# GPIO_Test.net
KiCad netlist of a schematic drawn in Altium Designer
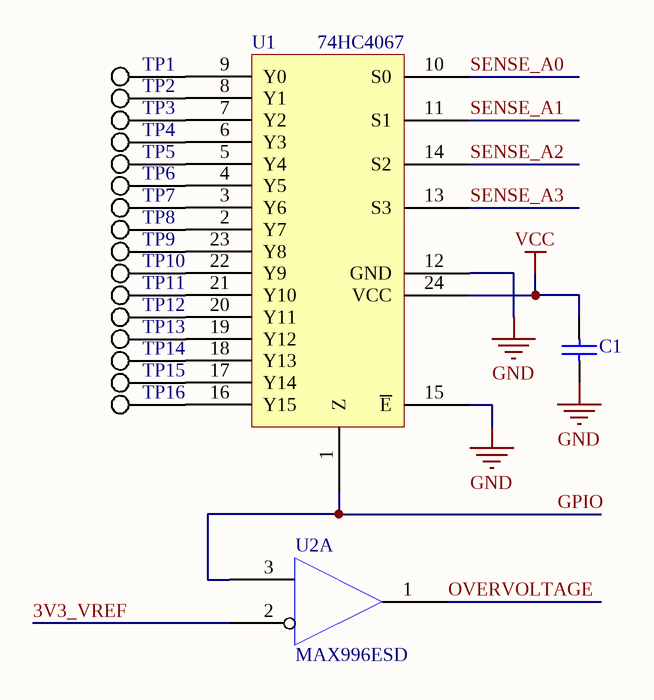
[diagram p0: GPIO Test.SchDoc]

(export (version "E")
  (design (tool "Eeschema 10.0.6"))
  (components
    (comp (ref "C1")
      (value "Cap chip")
      (footprint "CAPC3216")
      (description "Chip Capacitor")
      (fields (field (name "PUBLISHER") "Altium Limited"))
      (libsource (lib "Common Devices") (part "Cap chip"))
    )
    (comp (ref "TP1") (value "Test point") (libsource (lib "PCB_Project") (part "Pogo Test Pin")))
    (comp (ref "TP2") (value "Test point") (libsource (lib "PCB_Project") (part "Pogo Test Pin")))
    (comp (ref "TP3") (value "Test point") (libsource (lib "PCB_Project") (part "Pogo Test Pin")))
    (comp (ref "TP4") (value "Test point") (libsource (lib "PCB_Project") (part "Pogo Test Pin")))
    (comp (ref "TP5") (value "Test point") (libsource (lib "PCB_Project") (part "Pogo Test Pin")))
    (comp (ref "TP6") (value "Test point") (libsource (lib "PCB_Project") (part "Pogo Test Pin")))
    (comp (ref "TP7") (value "Test point") (libsource (lib "PCB_Project") (part "Pogo Test Pin")))
    (comp (ref "TP8") (value "Test point") (libsource (lib "PCB_Project") (part "Pogo Test Pin")))
    (comp (ref "TP9") (value "Test point") (libsource (lib "PCB_Project") (part "Pogo Test Pin")))
    (comp (ref "TP10") (value "Test point") (libsource (lib "PCB_Project") (part "Pogo Test Pin")))
    (comp (ref "TP11") (value "Test point") (libsource (lib "PCB_Project") (part "Pogo Test Pin")))
    (comp (ref "TP12") (value "Test point") (libsource (lib "PCB_Project") (part "Pogo Test Pin")))
    (comp (ref "TP13") (value "Test point") (libsource (lib "PCB_Project") (part "Pogo Test Pin")))
    (comp (ref "TP14") (value "Test point") (libsource (lib "PCB_Project") (part "Pogo Test Pin")))
    (comp (ref "TP15") (value "Test point") (libsource (lib "PCB_Project") (part "Pogo Test Pin")))
    (comp (ref "TP16") (value "Test point") (libsource (lib "PCB_Project") (part "Pogo Test Pin")))
    (comp (ref "U1")
      (value "74HC4067")
      (footprint "SO24")
      (description "16-channel analog multiplexer/demultiplexer")
      (libsource (lib "PCB_Project") (part "74HC4067; 74HCT4067"))
    )
    (comp (ref "U2")
      (value "MAX996ESD")
      (footprint "SOIC-14")
      (description "High-Speed, Micropower, Low-Voltage,  Rail-to-Rail I/O Comparators")
      (libsource (lib "PCB_Project") (part "MAX996ESD"))
    )
  )
  (nets
    (net (code "1") (name "/3V3_VREF") (class "Default")
      (node (ref "U2") (pin "2") (pinfunction "-IN1_2") (pintype "passive"))
    )
    (net (code "2") (name "/GPIO") (class "Default")
      (node (ref "U1") (pin "1") (pinfunction "Z_1") (pintype "passive"))
      (node (ref "U2") (pin "3") (pinfunction "+IN1_3") (pintype "passive"))
    )
    (net (code "3") (name "/OVERVOLTAGE") (class "Default")
      (node (ref "U2") (pin "1") (pinfunction "OUT1_1") (pintype "passive"))
    )
    (net (code "4") (name "/SENSE_A0") (class "Default")
      (node (ref "U1") (pin "10") (pinfunction "S0_10") (pintype "passive"))
    )
    (net (code "5") (name "/SENSE_A1") (class "Default")
      (node (ref "U1") (pin "11") (pinfunction "S1_11") (pintype "passive"))
    )
    (net (code "6") (name "/SENSE_A2") (class "Default")
      (node (ref "U1") (pin "14") (pinfunction "S2_14") (pintype "passive"))
    )
    (net (code "7") (name "/SENSE_A3") (class "Default")
      (node (ref "U1") (pin "13") (pinfunction "S3_13") (pintype "passive"))
    )
    (net (code "8") (name "GND") (class "Default")
      (node (ref "C1") (pin "1") (pinfunction "1_1") (pintype "passive"))
      (node (ref "U1") (pin "12") (pinfunction "GND_12") (pintype "passive"))
      (node (ref "U1") (pin "15") (pinfunction "~{E}_15") (pintype "passive"))
    )
    (net (code "9") (name "Net-(U1-Y0)") (class "Default")
      (node (ref "TP1") (pin "1") (pinfunction "1_1") (pintype "passive"))
      (node (ref "U1") (pin "9") (pinfunction "Y0_9") (pintype "passive"))
    )
    (net (code "10") (name "Net-(U1-Y1)") (class "Default")
      (node (ref "TP2") (pin "1") (pinfunction "1_1") (pintype "passive"))
      (node (ref "U1") (pin "8") (pinfunction "Y1_8") (pintype "passive"))
    )
    (net (code "11") (name "Net-(U1-Y2)") (class "Default")
      (node (ref "TP3") (pin "1") (pinfunction "1_1") (pintype "passive"))
      (node (ref "U1") (pin "7") (pinfunction "Y2_7") (pintype "passive"))
    )
    (net (code "12") (name "Net-(U1-Y3)") (class "Default")
      (node (ref "TP4") (pin "1") (pinfunction "1_1") (pintype "passive"))
      (node (ref "U1") (pin "6") (pinfunction "Y3_6") (pintype "passive"))
    )
    (net (code "13") (name "Net-(U1-Y4)") (class "Default")
      (node (ref "TP5") (pin "1") (pinfunction "1_1") (pintype "passive"))
      (node (ref "U1") (pin "5") (pinfunction "Y4_5") (pintype "passive"))
    )
    (net (code "14") (name "Net-(U1-Y5)") (class "Default")
      (node (ref "TP6") (pin "1") (pinfunction "1_1") (pintype "passive"))
      (node (ref "U1") (pin "4") (pinfunction "Y5_4") (pintype "passive"))
    )
    (net (code "15") (name "Net-(U1-Y6)") (class "Default")
      (node (ref "TP7") (pin "1") (pinfunction "1_1") (pintype "passive"))
      (node (ref "U1") (pin "3") (pinfunction "Y6_3") (pintype "passive"))
    )
    (net (code "16") (name "Net-(U1-Y7)") (class "Default")
      (node (ref "TP8") (pin "1") (pinfunction "1_1") (pintype "passive"))
      (node (ref "U1") (pin "2") (pinfunction "Y7_2") (pintype "passive"))
    )
    (net (code "17") (name "Net-(U1-Y8)") (class "Default")
      (node (ref "TP9") (pin "1") (pinfunction "1_1") (pintype "passive"))
      (node (ref "U1") (pin "23") (pinfunction "Y8_23") (pintype "passive"))
    )
    (net (code "18") (name "Net-(U1-Y9)") (class "Default")
      (node (ref "TP10") (pin "1") (pinfunction "1_1") (pintype "passive"))
      (node (ref "U1") (pin "22") (pinfunction "Y9_22") (pintype "passive"))
    )
    (net (code "19") (name "Net-(U1-Y10)") (class "Default")
      (node (ref "TP11") (pin "1") (pinfunction "1_1") (pintype "passive"))
      (node (ref "U1") (pin "21") (pinfunction "Y10_21") (pintype "passive"))
    )
    (net (code "20") (name "Net-(U1-Y11)") (class "Default")
      (node (ref "TP12") (pin "1") (pinfunction "1_1") (pintype "passive"))
      (node (ref "U1") (pin "20") (pinfunction "Y11_20") (pintype "passive"))
    )
    (net (code "21") (name "Net-(U1-Y12)") (class "Default")
      (node (ref "TP13") (pin "1") (pinfunction "1_1") (pintype "passive"))
      (node (ref "U1") (pin "19") (pinfunction "Y12_19") (pintype "passive"))
    )
    (net (code "22") (name "Net-(U1-Y13)") (class "Default")
      (node (ref "TP14") (pin "1") (pinfunction "1_1") (pintype "passive"))
      (node (ref "U1") (pin "18") (pinfunction "Y13_18") (pintype "passive"))
    )
    (net (code "23") (name "Net-(U1-Y14)") (class "Default")
      (node (ref "TP15") (pin "1") (pinfunction "1_1") (pintype "passive"))
      (node (ref "U1") (pin "17") (pinfunction "Y14_17") (pintype "passive"))
    )
    (net (code "24") (name "Net-(U1-Y15)") (class "Default")
      (node (ref "TP16") (pin "1") (pinfunction "1_1") (pintype "passive"))
      (node (ref "U1") (pin "16") (pinfunction "Y15_16") (pintype "passive"))
    )
    (net (code "25") (name "VCC") (class "Default")
      (node (ref "C1") (pin "2") (pinfunction "2_2") (pintype "passive"))
      (node (ref "U1") (pin "24") (pinfunction "VCC_24") (pintype "passive"))
    )
  )
)
